# NguyenLy.net
KiCad netlist of a schematic drawn in Altium Designer
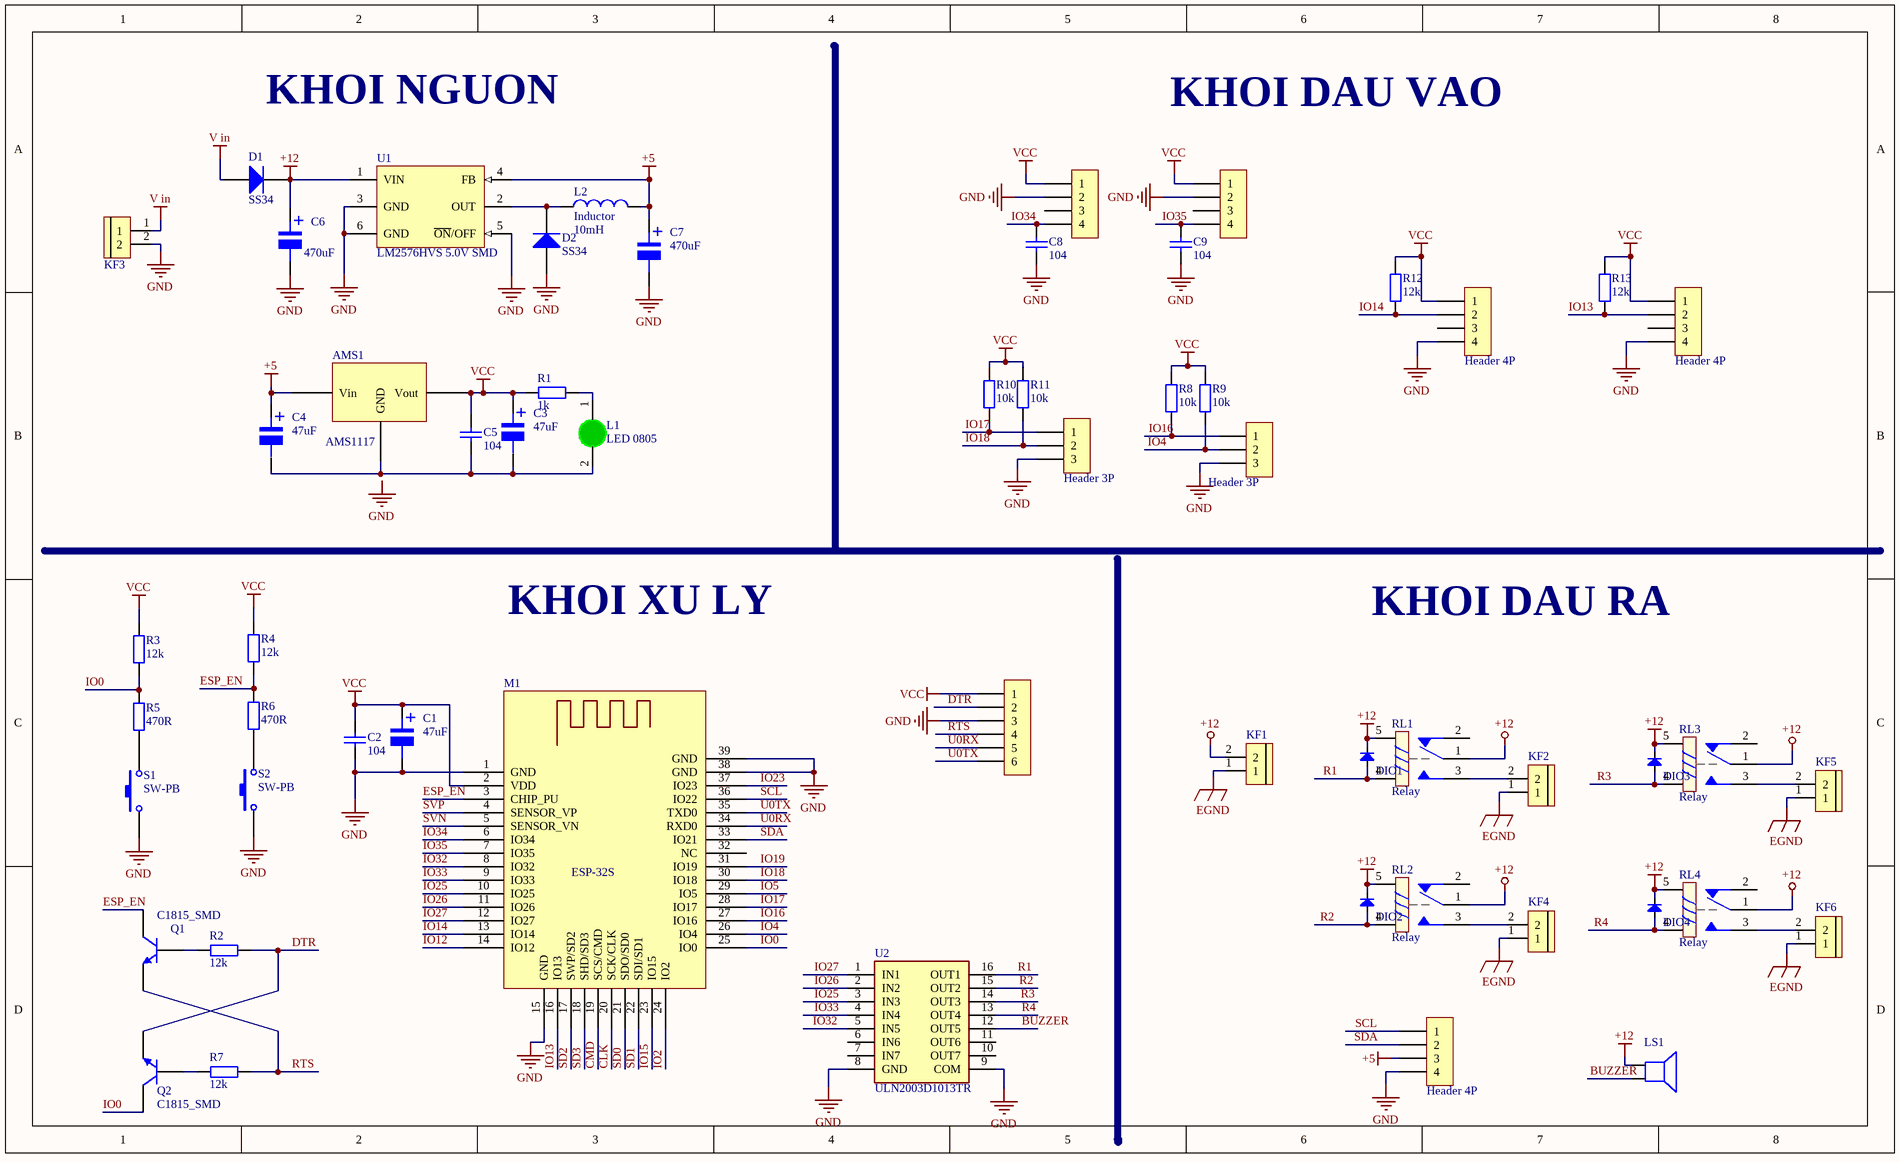
[diagram p0: NguyenLy.SchDoc]

(export (version "E")
  (design (tool "Eeschema 10.0.6"))
  (components
    (comp (ref "AMS1") (value "AMS1117") (footprint "TO 252") (libsource (lib "KN") (part "AMS1117")))
    (comp (ref "C1")
      (value "47uF")
      (footprint "tu nhom 6.3 (d)")
      (description "Dán")
      (libsource (lib "Altium_Lib_by_KhueNguyenCreator") (part "Tu Nhom 47uF 25V"))
    )
    (comp (ref "C2")
      (value "104")
      (footprint "tu 0805")
      (description "Dán")
      (libsource (lib "Altium_Lib_by_KhueNguyenCreator") (part "Tu 0805 104 50V 10%"))
    )
    (comp (ref "C3")
      (value "47uF")
      (footprint "tu nhom 6.3 (d)")
      (description "Dán")
      (libsource (lib "Altium_Lib_by_KhueNguyenCreator") (part "Tu Nhom 47uF 25V"))
    )
    (comp (ref "C4")
      (value "47uF")
      (footprint "tu nhom 6.3 (d)")
      (description "Dán")
      (libsource (lib "Altium_Lib_by_KhueNguyenCreator") (part "Tu Nhom 47uF 25V"))
    )
    (comp (ref "C5")
      (value "104")
      (footprint "tu 0805")
      (description "Dán")
      (libsource (lib "Altium_Lib_by_KhueNguyenCreator") (part "Tu 0805 104 50V 10%"))
    )
    (comp (ref "C6")
      (value "470uF")
      (footprint "tu nhom 6.3 (d)")
      (description "Dán")
      (libsource (lib "Altium_Lib_by_KhueNguyenCreator") (part "Tu Nhom 47uF 25V"))
    )
    (comp (ref "C7")
      (value "470uF")
      (footprint "tu nhom 6.3 (d)")
      (description "Dán")
      (libsource (lib "Altium_Lib_by_KhueNguyenCreator") (part "Tu Nhom 47uF 25V"))
    )
    (comp (ref "C8")
      (value "104")
      (footprint "tu 0805")
      (description "Dán")
      (libsource (lib "Altium_Lib_by_KhueNguyenCreator") (part "Tu 0805 104 50V 10%"))
    )
    (comp (ref "C9")
      (value "104")
      (footprint "tu 0805")
      (description "Dán")
      (libsource (lib "Altium_Lib_by_KhueNguyenCreator") (part "Tu 0805 104 50V 10%"))
    )
    (comp (ref "D1")
      (value "SS34")
      (footprint "DIODE SMA")
      (description "Dán")
      (libsource (lib "Altium_Lib_by_KhueNguyenCreator") (part "Diode SS34 ( 1N5822 )"))
    )
    (comp (ref "D2")
      (value "SS34")
      (footprint "DIODE SMA")
      (description "Dán")
      (libsource (lib "Altium_Lib_by_KhueNguyenCreator") (part "Diode SS34 ( 1N5822 )"))
    )
    (comp (ref "DIO1")
      (value "Diode SMD")
      (footprint "DIO-SMD-123")
      (description "Default Diode")
      (fields (field (name "PUBLISHER") "Altium Limited"))
      (libsource (lib "LIBRARY cad pro") (part "Diode SMD"))
    )
    (comp (ref "DIO2")
      (value "Diode SMD")
      (footprint "DIO-SMD-123")
      (description "Default Diode")
      (fields (field (name "PUBLISHER") "Altium Limited"))
      (libsource (lib "LIBRARY cad pro") (part "Diode SMD"))
    )
    (comp (ref "DIO3")
      (value "Diode SMD")
      (footprint "DIO-SMD-123")
      (description "Default Diode")
      (fields (field (name "PUBLISHER") "Altium Limited"))
      (libsource (lib "LIBRARY cad pro") (part "Diode SMD"))
    )
    (comp (ref "DIO4")
      (value "Diode SMD")
      (footprint "DIO-SMD-123")
      (description "Default Diode")
      (fields (field (name "PUBLISHER") "Altium Limited"))
      (libsource (lib "LIBRARY cad pro") (part "Diode SMD"))
    )
    (comp (ref "H1")
      (value "Header 6P 2.54 Duc Cong")
      (footprint "Header 6P DC 2.54")
      (description "C?m")
      (libsource (lib "Altium_Lib_by_KhueNguyenCreator") (part "Header 6P 2.54 Duc Cong"))
    )
    (comp (ref "H2")
      (value "Header 4P")
      (footprint "Header 4P DC 2.54")
      (description "C?m")
      (libsource (lib "Altium_Lib_by_KhueNguyenCreator") (part "Header 4P 2.54 Duc Cong"))
    )
    (comp (ref "H3")
      (value "Header 4P 2.54 Duc Cong")
      (footprint "Header 4P DC 2.54")
      (description "C?m")
      (libsource (lib "Altium_Lib_by_KhueNguyenCreator") (part "Header 4P 2.54 Duc Cong"))
    )
    (comp (ref "H4")
      (value "Header 4P 2.54 Duc Cong")
      (footprint "Header 4P DC 2.54")
      (description "C?m")
      (libsource (lib "Altium_Lib_by_KhueNguyenCreator") (part "Header 4P 2.54 Duc Cong"))
    )
    (comp (ref "H5")
      (value "Header 4P")
      (footprint "Header 4P DC 2.54")
      (description "C?m")
      (libsource (lib "Altium_Lib_by_KhueNguyenCreator") (part "Header 4P 2.54 Duc Cong"))
    )
    (comp (ref "H6")
      (value "Header 4P")
      (footprint "Header 4P DC 2.54")
      (description "C?m")
      (libsource (lib "Altium_Lib_by_KhueNguyenCreator") (part "Header 4P 2.54 Duc Cong"))
    )
    (comp (ref "H7")
      (value "Header 3P")
      (footprint "Header 3P DC 2.54")
      (description "C?m")
      (libsource (lib "Altium_Lib_by_KhueNguyenCreator") (part "Header 3P 2.54 Duc Cong"))
    )
    (comp (ref "H8")
      (value "Header 3P")
      (footprint "Header 3P DC 2.54")
      (description "C?m")
      (libsource (lib "Altium_Lib_by_KhueNguyenCreator") (part "Header 3P 2.54 Duc Cong"))
    )
    (comp (ref "KF1")
      (value "CON 2 KF7.62")
      (footprint "CON 2 KF7.62")
      (description "C?m")
      (libsource (lib "Altium_Lib_by_KhueNguyenCreator") (part "CON 2 KF7.62"))
    )
    (comp (ref "KF2")
      (value "CON 2 KF7.62")
      (footprint "CON 2 KF7.62")
      (description "C?m")
      (libsource (lib "Altium_Lib_by_KhueNguyenCreator") (part "CON 2 KF7.62"))
    )
    (comp (ref "KF3")
      (value "CON 2 KF7.62")
      (footprint "CON 2 KF7.62")
      (description "C?m")
      (libsource (lib "") (part "CON 2 KF7.62_1"))
    )
    (comp (ref "KF4")
      (value "CON 2 KF7.62")
      (footprint "CON 2 KF7.62")
      (description "C?m")
      (libsource (lib "Altium_Lib_by_KhueNguyenCreator") (part "CON 2 KF7.62"))
    )
    (comp (ref "KF5")
      (value "CON 2 KF7.62")
      (footprint "CON 2 KF7.62")
      (description "C?m")
      (libsource (lib "Altium_Lib_by_KhueNguyenCreator") (part "CON 2 KF7.62"))
    )
    (comp (ref "KF6")
      (value "CON 2 KF7.62")
      (footprint "CON 2 KF7.62")
      (description "C?m")
      (libsource (lib "Altium_Lib_by_KhueNguyenCreator") (part "CON 2 KF7.62"))
    )
    (comp (ref "L1")
      (value "LED 0805")
      (footprint "LED-0805-Green")
      (description "Dán")
      (libsource (lib "Altium_Lib_by_KhueNguyenCreator") (part "LED 0805 Xanh La"))
    )
    (comp (ref "L2")
      (value "Inductor")
      (footprint "MinhTien_PcbLib:INDC_L127H_331")
      (fields (field (name "ALTIUM_VALUE") "10mH") (field (name "PUBLISHER") "Altium Limited"))
      (libsource (lib "MinhTien_SCHLib") (part "Inductor"))
    )
    (comp (ref "LS1")
      (value "Coi Chip Speaker")
      (footprint "Coi Chip Speacker")
      (description "Còi chip")
      (libsource (lib "Altium_Lib_by_KhueNguyenCreator") (part "Coi Chip Speaker"))
    )
    (comp (ref "M1")
      (value "ESP-32S")
      (footprint "ESP-32S")
      (libsource (lib "MinhTien_SCHLib") (part "WIFI_ESP-32S"))
    )
    (comp (ref "Q1")
      (value "C1815_SMD")
      (footprint "MinhTien_PcbLib:SOT23")
      (description "NPN General Purpose Amplifier")
      (fields (field (name "PUBLISHER") "Altium Limited"))
      (libsource (lib "MinhTien_SCHLib") (part "C1815_SMD"))
    )
    (comp (ref "Q2")
      (value "C1815_SMD")
      (footprint "MinhTien_PcbLib:SOT23")
      (description "NPN General Purpose Amplifier")
      (fields (field (name "PUBLISHER") "Altium Limited"))
      (libsource (lib "MinhTien_SCHLib") (part "C1815_SMD"))
    )
    (comp (ref "R1")
      (value "1k")
      (footprint "tro smd 0805")
      (description "Dán")
      (libsource (lib "Altium_Lib_by_KhueNguyenCreator") (part "Tro 0805 1% 1k"))
    )
    (comp (ref "R2")
      (value "12k")
      (footprint "tro smd 0805")
      (description "Dán")
      (libsource (lib "Altium_Lib_by_KhueNguyenCreator") (part "Tro 0805 5% 12k"))
    )
    (comp (ref "R3")
      (value "12k")
      (footprint "tro smd 0805")
      (description "Dán")
      (libsource (lib "Altium_Lib_by_KhueNguyenCreator") (part "Tro 0805 5% 12k"))
    )
    (comp (ref "R4")
      (value "12k")
      (footprint "tro smd 0805")
      (description "Dán")
      (libsource (lib "Altium_Lib_by_KhueNguyenCreator") (part "Tro 0805 5% 12k"))
    )
    (comp (ref "R5")
      (value "470R")
      (footprint "Tro SMD 0805")
      (description "Dán")
      (libsource (lib "Altium_Lib_by_KhueNguyenCreator") (part "Tro 0805 5% 470R"))
    )
    (comp (ref "R6")
      (value "470R")
      (footprint "Tro SMD 0805")
      (description "Dán")
      (libsource (lib "Altium_Lib_by_KhueNguyenCreator") (part "Tro 0805 5% 470R"))
    )
    (comp (ref "R7")
      (value "12k")
      (footprint "tro smd 0805")
      (description "Dán")
      (libsource (lib "Altium_Lib_by_KhueNguyenCreator") (part "Tro 0805 5% 12k"))
    )
    (comp (ref "R8")
      (value "10k")
      (footprint "tro smd 0805")
      (description "Dán")
      (libsource (lib "Altium_Lib_by_KhueNguyenCreator") (part "Tro 0805 1% 10k"))
    )
    (comp (ref "R9")
      (value "10k")
      (footprint "tro smd 0805")
      (description "Dán")
      (libsource (lib "Altium_Lib_by_KhueNguyenCreator") (part "Tro 0805 1% 10k"))
    )
    (comp (ref "R10")
      (value "10k")
      (footprint "tro smd 0805")
      (description "Dán")
      (libsource (lib "Altium_Lib_by_KhueNguyenCreator") (part "Tro 0805 1% 10k"))
    )
    (comp (ref "R11")
      (value "10k")
      (footprint "tro smd 0805")
      (description "Dán")
      (libsource (lib "Altium_Lib_by_KhueNguyenCreator") (part "Tro 0805 1% 10k"))
    )
    (comp (ref "R12")
      (value "12k")
      (footprint "tro smd 0805")
      (description "Dán")
      (libsource (lib "Altium_Lib_by_KhueNguyenCreator") (part "Tro 0805 5% 12k"))
    )
    (comp (ref "R13")
      (value "12k")
      (footprint "tro smd 0805")
      (description "Dán")
      (libsource (lib "Altium_Lib_by_KhueNguyenCreator") (part "Tro 0805 5% 12k"))
    )
    (comp (ref "RL1")
      (value "Relay")
      (footprint "Relay 5 Chan SRD")
      (description "Relay 5 Chan")
      (libsource (lib "Altium_Lib_by_KhueNguyenCreator") (part "Relay 5 Chan SRD"))
    )
    (comp (ref "RL2")
      (value "Relay")
      (footprint "Relay 5 Chan SRD")
      (description "Relay 5 Chan")
      (libsource (lib "Altium_Lib_by_KhueNguyenCreator") (part "Relay 5 Chan SRD"))
    )
    (comp (ref "RL3")
      (value "Relay")
      (footprint "Relay 5 Chan SRD")
      (description "Relay 5 Chan")
      (libsource (lib "Altium_Lib_by_KhueNguyenCreator") (part "Relay 5 Chan SRD"))
    )
    (comp (ref "RL4")
      (value "Relay")
      (footprint "Relay 5 Chan SRD")
      (description "Relay 5 Chan")
      (libsource (lib "Altium_Lib_by_KhueNguyenCreator") (part "Relay 5 Chan SRD"))
    )
    (comp (ref "S1")
      (value "SW-PB")
      (footprint "MinhTien_PCBLib:SW-SMD")
      (description "Switch")
      (fields (field (name "PUBLISHER") "Altium Limited"))
      (libsource (lib "MinhTien_SCHLib") (part "SW-PB"))
    )
    (comp (ref "S2")
      (value "SW-PB")
      (footprint "MinhTien_PCBLib:SW-SMD")
      (description "Switch")
      (fields (field (name "PUBLISHER") "Altium Limited"))
      (libsource (lib "MinhTien_SCHLib") (part "SW-PB"))
    )
    (comp (ref "U1")
      (value "LM2576HVS 5.0V SMD")
      (footprint "TO263-5")
      (description "Dán")
      (libsource (lib "Altium_Lib_by_KhueNguyenCreator") (part "LM2576HVS 5.0V SMD"))
    )
    (comp (ref "U2")
      (value "ULN2003D1013TR")
      (footprint "SOIC16_50_284_25X90_SMT")
      (description "Bipolar (BJT) Transistor Array 7 NPN Darlington 50V 500mA Surface Mount 16-SO")
      (fields (field (name "MANUFACTURER") "STMicroelectronics"))
      (libsource (lib "Altium_Lib_by_KhueNguyenCreator") (part "IC_ULN2003D1013TR"))
    )
  )
  (nets
    (net (code "1") (name "+5") (class "Default")
      (node (ref "AMS1") (pin "3") (pinfunction "Vin_3") (pintype "passive"))
      (node (ref "C4") (pin "1") (pinfunction "1_1") (pintype "passive"))
      (node (ref "C7") (pin "1") (pinfunction "1_1") (pintype "passive"))
      (node (ref "H2") (pin "3") (pinfunction "3_3") (pintype "passive"))
      (node (ref "L2") (pin "2") (pinfunction "2_2") (pintype "passive"))
      (node (ref "U1") (pin "4") (pinfunction "FB_4") (pintype "input"))
    )
    (net (code "2") (name "+12") (class "Default")
      (node (ref "C6") (pin "1") (pinfunction "1_1") (pintype "passive"))
      (node (ref "D1") (pin "2") (pinfunction "K_2") (pintype "passive"))
      (node (ref "DIO1") (pin "2") (pinfunction "K_2") (pintype "passive"))
      (node (ref "DIO2") (pin "2") (pinfunction "K_2") (pintype "passive"))
      (node (ref "DIO3") (pin "2") (pinfunction "K_2") (pintype "passive"))
      (node (ref "DIO4") (pin "2") (pinfunction "K_2") (pintype "passive"))
      (node (ref "KF1") (pin "2") (pinfunction "2_2") (pintype "passive"))
      (node (ref "LS1") (pin "1") (pinfunction "1_1") (pintype "passive"))
      (node (ref "RL1") (pin "1") (pinfunction "1_1") (pintype "passive"))
      (node (ref "RL1") (pin "5") (pinfunction "5_5") (pintype "passive"))
      (node (ref "RL2") (pin "1") (pinfunction "1_1") (pintype "passive"))
      (node (ref "RL2") (pin "5") (pinfunction "5_5") (pintype "passive"))
      (node (ref "RL3") (pin "1") (pinfunction "1_1") (pintype "passive"))
      (node (ref "RL3") (pin "5") (pinfunction "5_5") (pintype "passive"))
      (node (ref "RL4") (pin "1") (pinfunction "1_1") (pintype "passive"))
      (node (ref "RL4") (pin "5") (pinfunction "5_5") (pintype "passive"))
      (node (ref "U1") (pin "1") (pinfunction "VIN_1") (pintype "power_in"))
    )
    (net (code "3") (name "/BUZZER") (class "Default")
      (node (ref "LS1") (pin "2") (pinfunction "2_2") (pintype "passive"))
      (node (ref "U2") (pin "12") (pinfunction "OUT5_12") (pintype "passive"))
    )
    (net (code "4") (name "/CLK") (class "Default")
      (node (ref "M1") (pin "20") (pinfunction "SCK/CLK_20") (pintype "passive"))
    )
    (net (code "5") (name "/CMD") (class "Default")
      (node (ref "M1") (pin "19") (pinfunction "SCS/CMD_19") (pintype "passive"))
    )
    (net (code "6") (name "/DTR") (class "Default")
      (node (ref "H1") (pin "2") (pinfunction "2_2") (pintype "passive"))
      (node (ref "Q2") (pin "2") (pinfunction "E_2") (pintype "passive"))
      (node (ref "R2") (pin "1") (pinfunction "1_1") (pintype "passive"))
    )
    (net (code "7") (name "/ESP_EN") (class "Default")
      (node (ref "M1") (pin "3") (pinfunction "CHIP_PU_3") (pintype "passive"))
      (node (ref "Q1") (pin "3") (pinfunction "C_3") (pintype "passive"))
      (node (ref "R4") (pin "1") (pinfunction "1_1") (pintype "passive"))
      (node (ref "R6") (pin "2") (pinfunction "2_2") (pintype "passive"))
    )
    (net (code "8") (name "/IO0") (class "Default")
      (node (ref "M1") (pin "25") (pinfunction "IO0_25") (pintype "passive"))
      (node (ref "Q2") (pin "3") (pinfunction "C_3") (pintype "passive"))
      (node (ref "R3") (pin "1") (pinfunction "1_1") (pintype "passive"))
      (node (ref "R5") (pin "2") (pinfunction "2_2") (pintype "passive"))
    )
    (net (code "9") (name "/IO2") (class "Default")
      (node (ref "M1") (pin "24") (pinfunction "IO2_24") (pintype "passive"))
    )
    (net (code "10") (name "/IO4") (class "Default")
      (node (ref "H7") (pin "2") (pinfunction "2_2") (pintype "passive"))
      (node (ref "M1") (pin "26") (pinfunction "IO4_26") (pintype "passive"))
      (node (ref "R9") (pin "1") (pinfunction "1_1") (pintype "passive"))
    )
    (net (code "11") (name "/IO5") (class "Default")
      (node (ref "M1") (pin "29") (pinfunction "IO5_29") (pintype "passive"))
    )
    (net (code "12") (name "/IO12") (class "Default")
      (node (ref "M1") (pin "14") (pinfunction "IO12_14") (pintype "passive"))
    )
    (net (code "13") (name "/IO13") (class "Default")
      (node (ref "H6") (pin "2") (pinfunction "2_2") (pintype "passive"))
      (node (ref "M1") (pin "16") (pinfunction "IO13_16") (pintype "passive"))
      (node (ref "R13") (pin "2") (pinfunction "2_2") (pintype "passive"))
    )
    (net (code "14") (name "/IO14") (class "Default")
      (node (ref "H5") (pin "2") (pinfunction "2_2") (pintype "passive"))
      (node (ref "M1") (pin "13") (pinfunction "IO14_13") (pintype "passive"))
      (node (ref "R12") (pin "2") (pinfunction "2_2") (pintype "passive"))
    )
    (net (code "15") (name "/IO15") (class "Default")
      (node (ref "M1") (pin "23") (pinfunction "IO15_23") (pintype "passive"))
    )
    (net (code "16") (name "/IO16") (class "Default")
      (node (ref "H7") (pin "1") (pinfunction "1_1") (pintype "passive"))
      (node (ref "M1") (pin "27") (pinfunction "IO16_27") (pintype "passive"))
      (node (ref "R8") (pin "1") (pinfunction "1_1") (pintype "passive"))
    )
    (net (code "17") (name "/IO17") (class "Default")
      (node (ref "H8") (pin "1") (pinfunction "1_1") (pintype "passive"))
      (node (ref "M1") (pin "28") (pinfunction "IO17_28") (pintype "passive"))
      (node (ref "R10") (pin "1") (pinfunction "1_1") (pintype "passive"))
    )
    (net (code "18") (name "/IO18") (class "Default")
      (node (ref "H8") (pin "2") (pinfunction "2_2") (pintype "passive"))
      (node (ref "M1") (pin "30") (pinfunction "IO18_30") (pintype "passive"))
      (node (ref "R11") (pin "1") (pinfunction "1_1") (pintype "passive"))
    )
    (net (code "19") (name "/IO19") (class "Default")
      (node (ref "M1") (pin "31") (pinfunction "IO19_31") (pintype "passive"))
    )
    (net (code "20") (name "/IO23") (class "Default")
      (node (ref "M1") (pin "37") (pinfunction "IO23_37") (pintype "passive"))
    )
    (net (code "21") (name "/IO25") (class "Default")
      (node (ref "M1") (pin "10") (pinfunction "IO25_10") (pintype "passive"))
      (node (ref "U2") (pin "3") (pinfunction "IN3_3") (pintype "passive"))
    )
    (net (code "22") (name "/IO26") (class "Default")
      (node (ref "M1") (pin "11") (pinfunction "IO26_11") (pintype "passive"))
      (node (ref "U2") (pin "2") (pinfunction "IN2_2") (pintype "passive"))
    )
    (net (code "23") (name "/IO27") (class "Default")
      (node (ref "M1") (pin "12") (pinfunction "IO27_12") (pintype "passive"))
      (node (ref "U2") (pin "1") (pinfunction "IN1_1") (pintype "passive"))
    )
    (net (code "24") (name "/IO32") (class "Default")
      (node (ref "M1") (pin "8") (pinfunction "IO32_8") (pintype "passive"))
      (node (ref "U2") (pin "5") (pinfunction "IN5_5") (pintype "passive"))
    )
    (net (code "25") (name "/IO33") (class "Default")
      (node (ref "M1") (pin "9") (pinfunction "IO33_9") (pintype "passive"))
      (node (ref "U2") (pin "4") (pinfunction "IN4_4") (pintype "passive"))
    )
    (net (code "26") (name "/IO34") (class "Default")
      (node (ref "C8") (pin "1") (pinfunction "1_1") (pintype "passive"))
      (node (ref "H3") (pin "4") (pinfunction "4_4") (pintype "passive"))
      (node (ref "M1") (pin "6") (pinfunction "IO34_6") (pintype "passive"))
    )
    (net (code "27") (name "/IO35") (class "Default")
      (node (ref "C9") (pin "1") (pinfunction "1_1") (pintype "passive"))
      (node (ref "H4") (pin "4") (pinfunction "4_4") (pintype "passive"))
      (node (ref "M1") (pin "7") (pinfunction "IO35_7") (pintype "passive"))
    )
    (net (code "28") (name "/R1") (class "Default")
      (node (ref "DIO1") (pin "1") (pinfunction "A_1") (pintype "passive"))
      (node (ref "RL1") (pin "4") (pinfunction "4_4") (pintype "passive"))
      (node (ref "U2") (pin "16") (pinfunction "OUT1_16") (pintype "passive"))
    )
    (net (code "29") (name "/R2") (class "Default")
      (node (ref "DIO2") (pin "1") (pinfunction "A_1") (pintype "passive"))
      (node (ref "RL2") (pin "4") (pinfunction "4_4") (pintype "passive"))
      (node (ref "U2") (pin "15") (pinfunction "OUT2_15") (pintype "passive"))
    )
    (net (code "30") (name "/R3") (class "Default")
      (node (ref "DIO3") (pin "1") (pinfunction "A_1") (pintype "passive"))
      (node (ref "RL3") (pin "4") (pinfunction "4_4") (pintype "passive"))
      (node (ref "U2") (pin "14") (pinfunction "OUT3_14") (pintype "passive"))
    )
    (net (code "31") (name "/R4") (class "Default")
      (node (ref "DIO4") (pin "1") (pinfunction "A_1") (pintype "passive"))
      (node (ref "RL4") (pin "4") (pinfunction "4_4") (pintype "passive"))
      (node (ref "U2") (pin "13") (pinfunction "OUT4_13") (pintype "passive"))
    )
    (net (code "32") (name "/RTS") (class "Default")
      (node (ref "H1") (pin "4") (pinfunction "4_4") (pintype "passive"))
      (node (ref "Q1") (pin "2") (pinfunction "E_2") (pintype "passive"))
      (node (ref "R7") (pin "1") (pinfunction "1_1") (pintype "passive"))
    )
    (net (code "33") (name "/SCL") (class "Default")
      (node (ref "H2") (pin "1") (pinfunction "1_1") (pintype "passive"))
      (node (ref "M1") (pin "36") (pinfunction "IO22_36") (pintype "passive"))
    )
    (net (code "34") (name "/SD0") (class "Default")
      (node (ref "M1") (pin "21") (pinfunction "SDO/SD0_21") (pintype "passive"))
    )
    (net (code "35") (name "/SD1") (class "Default")
      (node (ref "M1") (pin "22") (pinfunction "SDI/SD1_22") (pintype "passive"))
    )
    (net (code "36") (name "/SD2") (class "Default")
      (node (ref "M1") (pin "17") (pinfunction "SWP/SD2_17") (pintype "passive"))
    )
    (net (code "37") (name "/SD3") (class "Default")
      (node (ref "M1") (pin "18") (pinfunction "SHD/SD3_18") (pintype "passive"))
    )
    (net (code "38") (name "/SDA") (class "Default")
      (node (ref "H2") (pin "2") (pinfunction "2_2") (pintype "passive"))
      (node (ref "M1") (pin "33") (pinfunction "IO21_33") (pintype "passive"))
    )
    (net (code "39") (name "/SVN") (class "Default")
      (node (ref "M1") (pin "5") (pinfunction "SENSOR_VN_5") (pintype "passive"))
    )
    (net (code "40") (name "/SVP") (class "Default")
      (node (ref "M1") (pin "4") (pinfunction "SENSOR_VP_4") (pintype "passive"))
    )
    (net (code "41") (name "/U0RX") (class "Default")
      (node (ref "H1") (pin "5") (pinfunction "5_5") (pintype "passive"))
      (node (ref "M1") (pin "34") (pinfunction "RXD0_34") (pintype "passive"))
    )
    (net (code "42") (name "/U0TX") (class "Default")
      (node (ref "H1") (pin "6") (pinfunction "6_6") (pintype "passive"))
      (node (ref "M1") (pin "35") (pinfunction "TXD0_35") (pintype "passive"))
    )
    (net (code "43") (name "EGND") (class "Default")
      (node (ref "KF1") (pin "1") (pinfunction "1_1") (pintype "passive"))
      (node (ref "KF2") (pin "1") (pinfunction "1_1") (pintype "passive"))
      (node (ref "KF4") (pin "1") (pinfunction "1_1") (pintype "passive"))
      (node (ref "KF5") (pin "1") (pinfunction "1_1") (pintype "passive"))
      (node (ref "KF6") (pin "1") (pinfunction "1_1") (pintype "passive"))
    )
    (net (code "44") (name "GND") (class "Default")
      (node (ref "C1") (pin "2") (pinfunction "2_2") (pintype "passive"))
      (node (ref "C2") (pin "2") (pinfunction "2_2") (pintype "passive"))
      (node (ref "C6") (pin "2") (pinfunction "2_2") (pintype "passive"))
      (node (ref "C7") (pin "2") (pinfunction "2_2") (pintype "passive"))
      (node (ref "C8") (pin "2") (pinfunction "2_2") (pintype "passive"))
      (node (ref "C9") (pin "2") (pinfunction "2_2") (pintype "passive"))
      (node (ref "D2") (pin "1") (pinfunction "A_1") (pintype "passive"))
      (node (ref "H1") (pin "3") (pinfunction "3_3") (pintype "passive"))
      (node (ref "H2") (pin "4") (pinfunction "4_4") (pintype "passive"))
      (node (ref "H3") (pin "2") (pinfunction "2_2") (pintype "passive"))
      (node (ref "H4") (pin "2") (pinfunction "2_2") (pintype "passive"))
      (node (ref "H5") (pin "4") (pinfunction "4_4") (pintype "passive"))
      (node (ref "H6") (pin "4") (pinfunction "4_4") (pintype "passive"))
      (node (ref "H7") (pin "3") (pinfunction "3_3") (pintype "passive"))
      (node (ref "H8") (pin "3") (pinfunction "3_3") (pintype "passive"))
      (node (ref "KF3") (pin "2") (pinfunction "2_2") (pintype "passive"))
      (node (ref "M1") (pin "1") (pinfunction "GND_1") (pintype "passive"))
      (node (ref "M1") (pin "15") (pinfunction "GND_15") (pintype "passive"))
      (node (ref "M1") (pin "38") (pinfunction "GND_38") (pintype "passive"))
      (node (ref "M1") (pin "39") (pinfunction "GND_39") (pintype "passive"))
      (node (ref "S1") (pin "1") (pinfunction "1_1") (pintype "passive"))
      (node (ref "S2") (pin "1") (pinfunction "1_1") (pintype "passive"))
      (node (ref "U1") (pin "3") (pinfunction "GND_3") (pintype "power_in"))
      (node (ref "U1") (pin "5") (pinfunction "~{ON}/OFF_5") (pintype "input"))
      (node (ref "U1") (pin "6") (pinfunction "GND_6") (pintype "passive"))
      (node (ref "U2") (pin "8") (pinfunction "GND_8") (pintype "passive"))
      (node (ref "U2") (pin "9") (pinfunction "COM_9") (pintype "passive"))
    )
    (net (code "45") (name "Net-(AMS1-GND)") (class "Default")
      (node (ref "AMS1") (pin "1") (pinfunction "GND_1") (pintype "passive"))
      (node (ref "C3") (pin "2") (pinfunction "2_2") (pintype "passive"))
      (node (ref "C4") (pin "2") (pinfunction "2_2") (pintype "passive"))
      (node (ref "C5") (pin "2") (pinfunction "2_2") (pintype "passive"))
      (node (ref "L1") (pin "2") (pinfunction "K_2") (pintype "passive"))
    )
    (net (code "46") (name "Net-(D2-K)") (class "Default")
      (node (ref "D2") (pin "2") (pinfunction "K_2") (pintype "passive"))
      (node (ref "L2") (pin "1") (pinfunction "1_1") (pintype "passive"))
      (node (ref "U1") (pin "2") (pinfunction "OUT_2") (pintype "power_in"))
    )
    (net (code "47") (name "Net-(KF2-Pad2)") (class "Default")
      (node (ref "KF2") (pin "2") (pinfunction "2_2") (pintype "passive"))
      (node (ref "RL1") (pin "3") (pinfunction "3_3") (pintype "passive"))
    )
    (net (code "48") (name "Net-(KF4-Pad2)") (class "Default")
      (node (ref "KF4") (pin "2") (pinfunction "2_2") (pintype "passive"))
      (node (ref "RL2") (pin "3") (pinfunction "3_3") (pintype "passive"))
    )
    (net (code "49") (name "Net-(KF5-Pad2)") (class "Default")
      (node (ref "KF5") (pin "2") (pinfunction "2_2") (pintype "passive"))
      (node (ref "RL3") (pin "3") (pinfunction "3_3") (pintype "passive"))
    )
    (net (code "50") (name "Net-(KF6-Pad2)") (class "Default")
      (node (ref "KF6") (pin "2") (pinfunction "2_2") (pintype "passive"))
      (node (ref "RL4") (pin "3") (pinfunction "3_3") (pintype "passive"))
    )
    (net (code "51") (name "Net-(L1-A)") (class "Default")
      (node (ref "L1") (pin "1") (pinfunction "A_1") (pintype "passive"))
      (node (ref "R1") (pin "2") (pinfunction "2_2") (pintype "passive"))
    )
    (net (code "52") (name "Net-(Q1-B)") (class "Default")
      (node (ref "Q1") (pin "1") (pinfunction "B_1") (pintype "passive"))
      (node (ref "R2") (pin "2") (pinfunction "2_2") (pintype "passive"))
    )
    (net (code "53") (name "Net-(Q2-B)") (class "Default")
      (node (ref "Q2") (pin "1") (pinfunction "B_1") (pintype "passive"))
      (node (ref "R7") (pin "2") (pinfunction "2_2") (pintype "passive"))
    )
    (net (code "54") (name "Net-(R5-Pad1)") (class "Default")
      (node (ref "R5") (pin "1") (pinfunction "1_1") (pintype "passive"))
      (node (ref "S1") (pin "2") (pinfunction "2_2") (pintype "passive"))
    )
    (net (code "55") (name "Net-(R6-Pad1)") (class "Default")
      (node (ref "R6") (pin "1") (pinfunction "1_1") (pintype "passive"))
      (node (ref "S2") (pin "2") (pinfunction "2_2") (pintype "passive"))
    )
    (net (code "56") (name "V in") (class "Default")
      (node (ref "D1") (pin "1") (pinfunction "A_1") (pintype "passive"))
      (node (ref "KF3") (pin "1") (pinfunction "1_1") (pintype "passive"))
    )
    (net (code "57") (name "VCC") (class "Default")
      (node (ref "AMS1") (pin "2") (pinfunction "Vout_2") (pintype "passive"))
      (node (ref "C1") (pin "1") (pinfunction "1_1") (pintype "passive"))
      (node (ref "C2") (pin "1") (pinfunction "1_1") (pintype "passive"))
      (node (ref "C3") (pin "1") (pinfunction "1_1") (pintype "passive"))
      (node (ref "C5") (pin "1") (pinfunction "1_1") (pintype "passive"))
      (node (ref "H1") (pin "1") (pinfunction "1_1") (pintype "passive"))
      (node (ref "H3") (pin "1") (pinfunction "1_1") (pintype "passive"))
      (node (ref "H4") (pin "1") (pinfunction "1_1") (pintype "passive"))
      (node (ref "H5") (pin "1") (pinfunction "1_1") (pintype "passive"))
      (node (ref "H6") (pin "1") (pinfunction "1_1") (pintype "passive"))
      (node (ref "M1") (pin "2") (pinfunction "VDD_2") (pintype "passive"))
      (node (ref "R1") (pin "1") (pinfunction "1_1") (pintype "passive"))
      (node (ref "R10") (pin "2") (pinfunction "2_2") (pintype "passive"))
      (node (ref "R11") (pin "2") (pinfunction "2_2") (pintype "passive"))
      (node (ref "R12") (pin "1") (pinfunction "1_1") (pintype "passive"))
      (node (ref "R13") (pin "1") (pinfunction "1_1") (pintype "passive"))
      (node (ref "R3") (pin "2") (pinfunction "2_2") (pintype "passive"))
      (node (ref "R4") (pin "2") (pinfunction "2_2") (pintype "passive"))
      (node (ref "R8") (pin "2") (pinfunction "2_2") (pintype "passive"))
      (node (ref "R9") (pin "2") (pinfunction "2_2") (pintype "passive"))
    )
    (net (code "58") (name "unconnected-(H3-Pad3)") (class "Default")
      (node (ref "H3") (pin "3") (pinfunction "3_3") (pintype "passive"))
    )
    (net (code "59") (name "unconnected-(H4-Pad3)") (class "Default")
      (node (ref "H4") (pin "3") (pinfunction "3_3") (pintype "passive"))
    )
    (net (code "60") (name "unconnected-(H5-Pad3)") (class "Default")
      (node (ref "H5") (pin "3") (pinfunction "3_3") (pintype "passive"))
    )
    (net (code "61") (name "unconnected-(H6-Pad3)") (class "Default")
      (node (ref "H6") (pin "3") (pinfunction "3_3") (pintype "passive"))
    )
    (net (code "62") (name "unconnected-(M1-NC-Pad32)") (class "Default")
      (node (ref "M1") (pin "32") (pinfunction "NC_32") (pintype "passive"))
    )
    (net (code "63") (name "unconnected-(RL1-Pad2)") (class "Default")
      (node (ref "RL1") (pin "2") (pinfunction "2_2") (pintype "passive"))
    )
    (net (code "64") (name "unconnected-(RL2-Pad2)") (class "Default")
      (node (ref "RL2") (pin "2") (pinfunction "2_2") (pintype "passive"))
    )
    (net (code "65") (name "unconnected-(RL3-Pad2)") (class "Default")
      (node (ref "RL3") (pin "2") (pinfunction "2_2") (pintype "passive"))
    )
    (net (code "66") (name "unconnected-(RL4-Pad2)") (class "Default")
      (node (ref "RL4") (pin "2") (pinfunction "2_2") (pintype "passive"))
    )
    (net (code "67") (name "unconnected-(U2-IN6-Pad6)") (class "Default")
      (node (ref "U2") (pin "6") (pinfunction "IN6_6") (pintype "passive"))
    )
    (net (code "68") (name "unconnected-(U2-IN7-Pad7)") (class "Default")
      (node (ref "U2") (pin "7") (pinfunction "IN7_7") (pintype "passive"))
    )
    (net (code "69") (name "unconnected-(U2-OUT6-Pad11)") (class "Default")
      (node (ref "U2") (pin "11") (pinfunction "OUT6_11") (pintype "passive"))
    )
    (net (code "70") (name "unconnected-(U2-OUT7-Pad10)") (class "Default")
      (node (ref "U2") (pin "10") (pinfunction "OUT7_10") (pintype "passive"))
    )
  )
)
